# TIDA-00643_C2000.net
KiCad netlist of a schematic drawn in Altium Designer
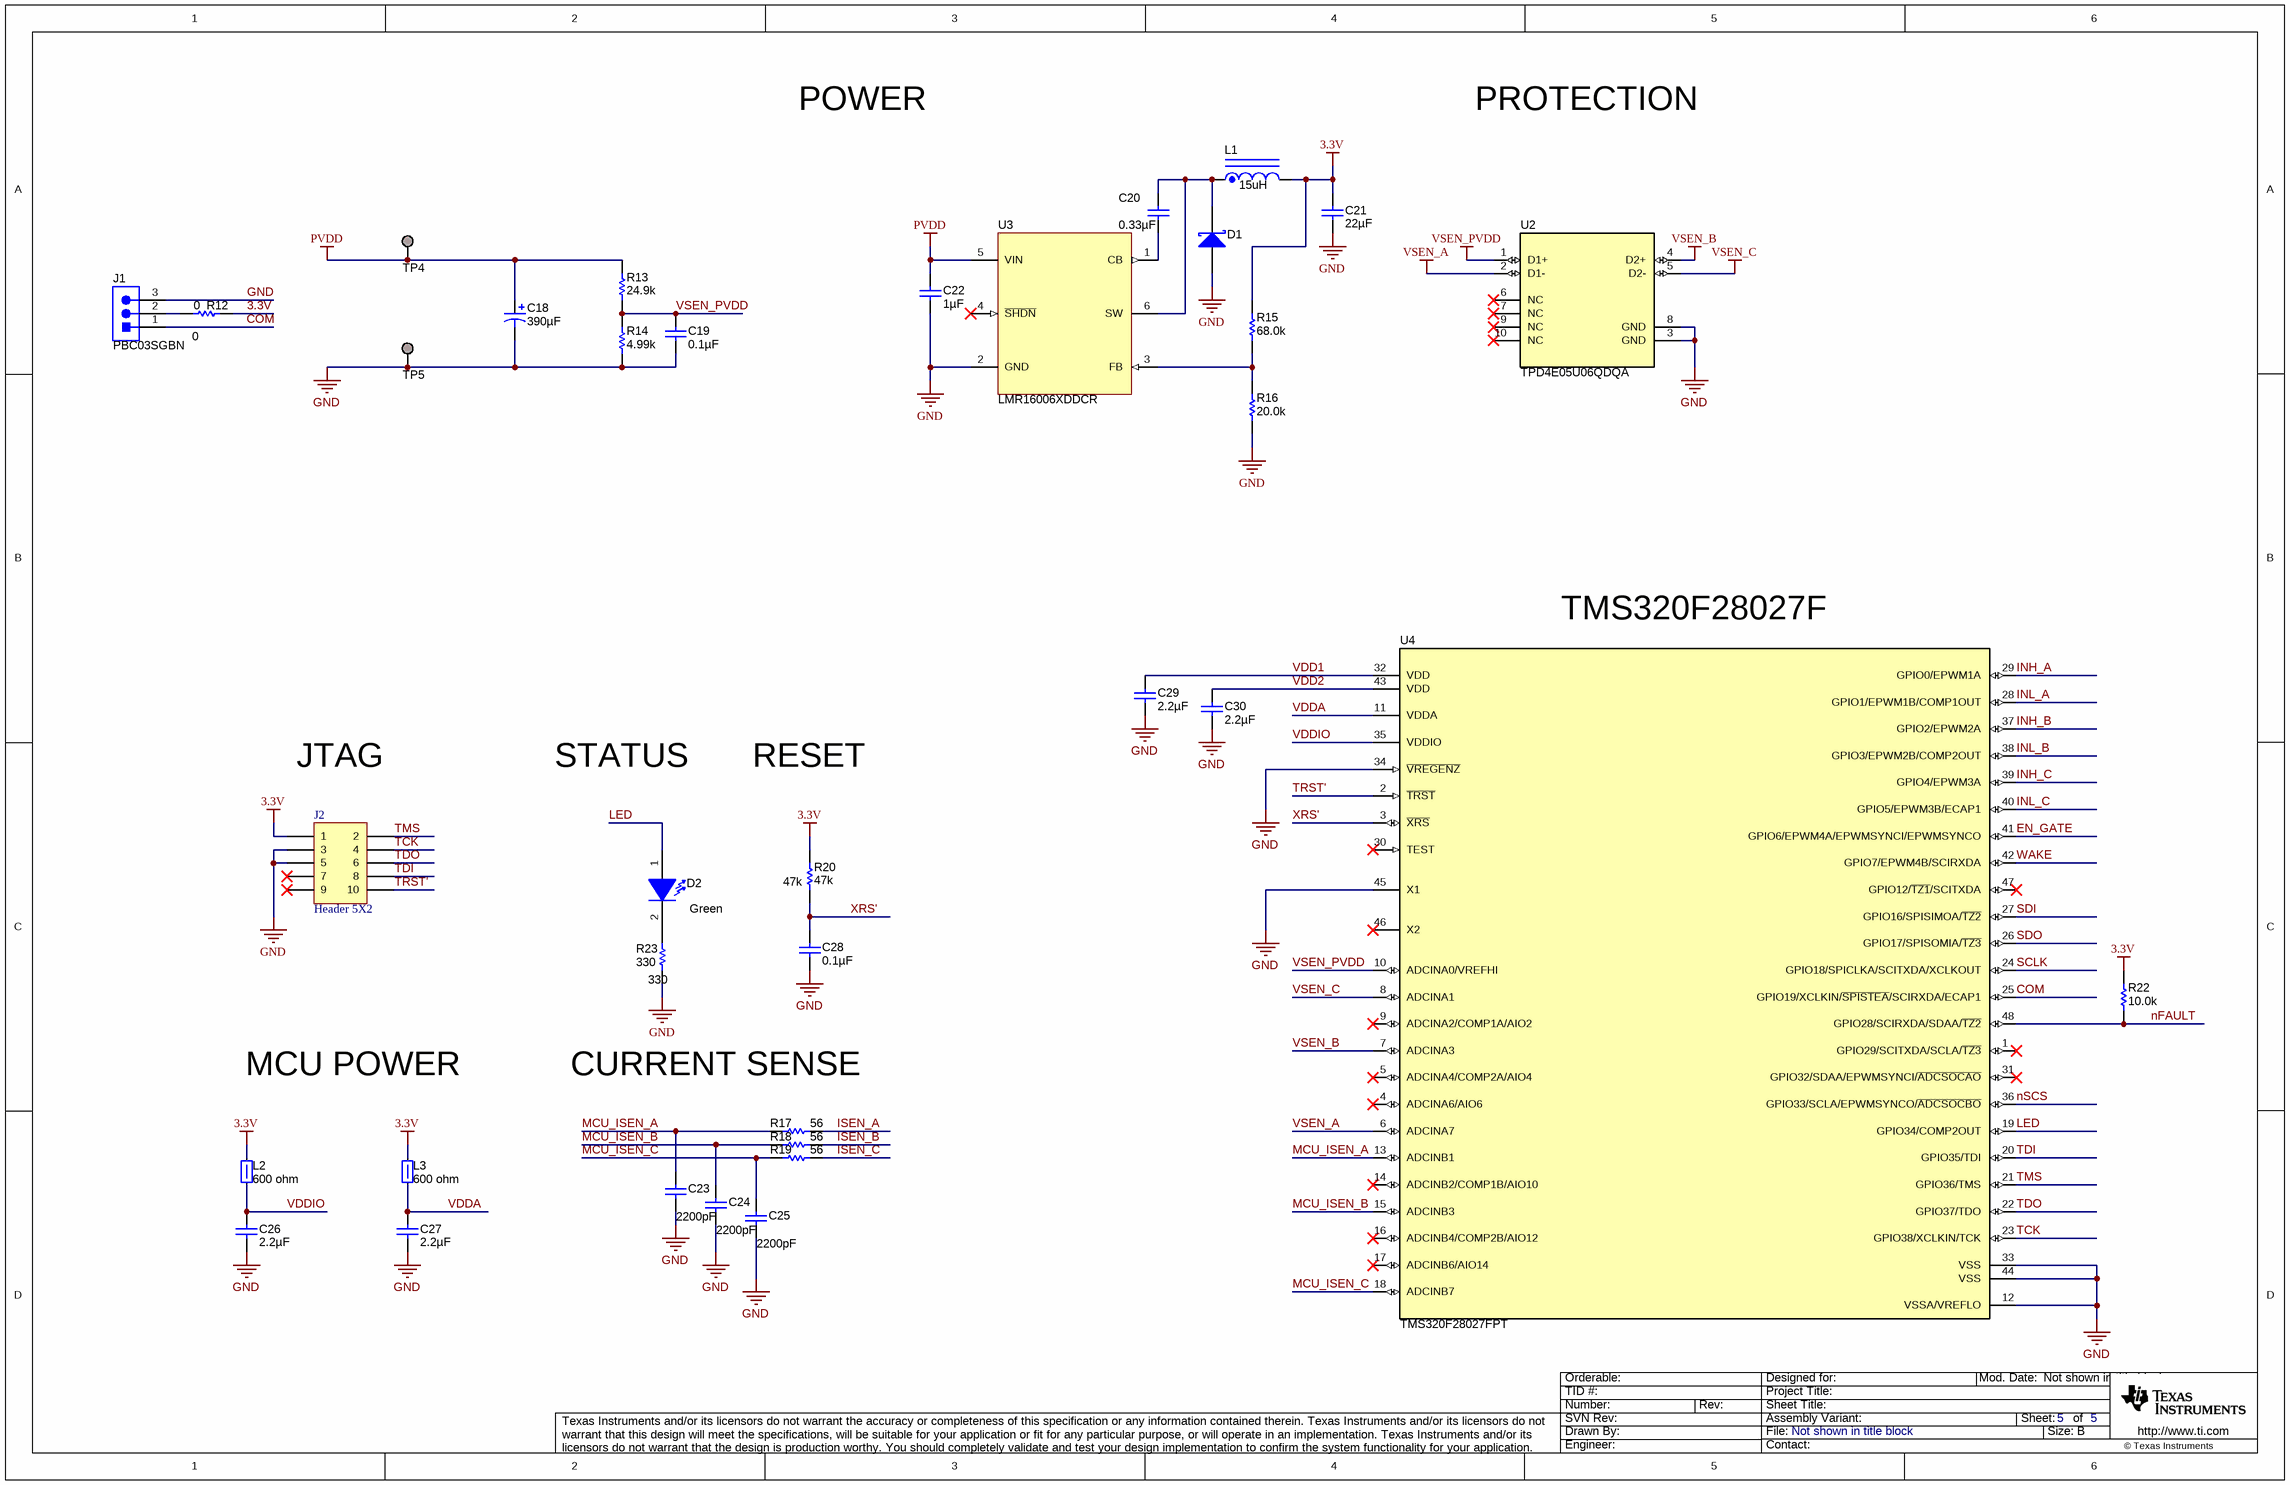
[diagram p0: TIDA-00643_C2000.SchDoc]

(export (version "E")
  (design (tool "Eeschema 10.0.6"))
  (components
    (comp (ref "C18")
      (value "EEE-FPV391UAP")
      (footprint "CAPAE1030X1080")
      (description "CAP, AL, 390 µF, 35 V, +/- 20%, 0.08 ohm, SMD")
      (fields
        (field (name "VALUEDISPLAYED") "390µF")
        (field (name "MANUFACTURER") "Panasonic")
        (field (name "PUBLISHER") "Texas Instruments")
      )
      (libsource (lib "Capacitor_Aluminum") (part "EEE-FPV391UAP"))
    )
    (comp (ref "C19")
      (value "885012105016")
      (footprint "0402L")
      (description "CAP, CERM, 0.1 µF, 16 V, +/- 20%, X5R, 0402")
      (fields
        (field (name "VALUEDISPLAYED") "0.1µF")
        (field (name "MANUFACTURER") "Wurth Elektronik")
        (field (name "PUBLISHER") "Texas Instruments")
      )
      (libsource (lib "Capacitor_Ceramic") (part "885012105016"))
    )
    (comp (ref "C20")
      (value "C0603C334Z3VACTU")
      (footprint "0603L")
      (description "CAP, CERM, 0.33 µF, 25 V, +80/-20%, Y5V, 0603")
      (fields
        (field (name "VALUEDISPLAYED") "0.33µF")
        (field (name "MANUFACTURER") "Kemet")
        (field (name "PUBLISHER") "Texas Instruments")
      )
      (libsource (lib "Capacitor_Ceramic") (part "C0603C334Z3VACTU"))
    )
    (comp (ref "C21")
      (value "C2012X5R1C226K125AC")
      (footprint "0805L")
      (description "CAP, CERM, 22 µF, 16 V, +/- 10%, X5R, 0805")
      (fields
        (field (name "VALUEDISPLAYED") "22µF")
        (field (name "MANUFACTURER") "TDK")
        (field (name "PUBLISHER") "Texas Instruments")
      )
      (libsource (lib "Capacitor_Ceramic") (part "C2012X5R1C226K125AC"))
    )
    (comp (ref "C22")
      (value "GMK107BJ105KA-T")
      (footprint "0603L")
      (description "CAP, CERM, 1 µF, 35 V, +/- 10%, X5R, 0603")
      (fields
        (field (name "VALUEDISPLAYED") "1µF")
        (field (name "MANUFACTURER") "Taiyo Yuden")
        (field (name "PUBLISHER") "Texas Instruments")
      )
      (libsource (lib "Capacitor_Ceramic") (part "GMK107BJ105KA-T"))
    )
    (comp (ref "C23")
      (value "GRM155R71C222KA01D")
      (footprint "0402L")
      (description "CAP, CERM, 2200 pF, 16 V, +/- 10%, X7R, 0402")
      (fields
        (field (name "VALUEDISPLAYED") "2200pF")
        (field (name "MANUFACTURER") "MuRata")
        (field (name "PUBLISHER") "Texas Instruments")
      )
      (libsource (lib "Capacitor_Ceramic") (part "GRM155R71C222KA01D"))
    )
    (comp (ref "C24")
      (value "GRM155R71C222KA01D")
      (footprint "0402L")
      (description "CAP, CERM, 2200 pF, 16 V, +/- 10%, X7R, 0402")
      (fields
        (field (name "VALUEDISPLAYED") "2200pF")
        (field (name "MANUFACTURER") "MuRata")
        (field (name "PUBLISHER") "Texas Instruments")
      )
      (libsource (lib "Capacitor_Ceramic") (part "GRM155R71C222KA01D"))
    )
    (comp (ref "C25")
      (value "GRM155R71C222KA01D")
      (footprint "0402L")
      (description "CAP, CERM, 2200 pF, 16 V, +/- 10%, X7R, 0402")
      (fields
        (field (name "VALUEDISPLAYED") "2200pF")
        (field (name "MANUFACTURER") "MuRata")
        (field (name "PUBLISHER") "Texas Instruments")
      )
      (libsource (lib "Capacitor_Ceramic") (part "GRM155R71C222KA01D"))
    )
    (comp (ref "C26")
      (value "GRM188R61C225KE15D")
      (footprint "0603L")
      (description "CAP, CERM, 2.2 µF, 16 V, +/- 10%, X5R, 0603")
      (fields
        (field (name "VALUEDISPLAYED") "2.2µF")
        (field (name "MANUFACTURER") "MuRata")
        (field (name "PUBLISHER") "Texas Instruments")
      )
      (libsource (lib "Capacitor_Ceramic") (part "GRM188R61C225KE15D"))
    )
    (comp (ref "C27")
      (value "GRM188R61C225KE15D")
      (footprint "0603L")
      (description "CAP, CERM, 2.2 µF, 16 V, +/- 10%, X5R, 0603")
      (fields
        (field (name "VALUEDISPLAYED") "2.2µF")
        (field (name "MANUFACTURER") "MuRata")
        (field (name "PUBLISHER") "Texas Instruments")
      )
      (libsource (lib "Capacitor_Ceramic") (part "GRM188R61C225KE15D"))
    )
    (comp (ref "C28")
      (value "885012105016")
      (footprint "0402L")
      (description "CAP, CERM, 0.1 µF, 16 V, +/- 20%, X5R, 0402")
      (fields
        (field (name "VALUEDISPLAYED") "0.1µF")
        (field (name "MANUFACTURER") "Wurth Elektronik")
        (field (name "PUBLISHER") "Texas Instruments")
      )
      (libsource (lib "Capacitor_Ceramic") (part "885012105016"))
    )
    (comp (ref "C29")
      (value "GRM188R61C225KE15D")
      (footprint "0603L")
      (description "CAP, CERM, 2.2 µF, 16 V, +/- 10%, X5R, 0603")
      (fields
        (field (name "VALUEDISPLAYED") "2.2µF")
        (field (name "MANUFACTURER") "MuRata")
        (field (name "PUBLISHER") "Texas Instruments")
      )
      (libsource (lib "Capacitor_Ceramic") (part "GRM188R61C225KE15D"))
    )
    (comp (ref "C30")
      (value "GRM188R61C225KE15D")
      (footprint "0603L")
      (description "CAP, CERM, 2.2 µF, 16 V, +/- 10%, X5R, 0603")
      (fields
        (field (name "VALUEDISPLAYED") "2.2µF")
        (field (name "MANUFACTURER") "MuRata")
        (field (name "PUBLISHER") "Texas Instruments")
      )
      (libsource (lib "Capacitor_Ceramic") (part "GRM188R61C225KE15D"))
    )
    (comp (ref "D1")
      (value "MBR1H100SFT3G")
      (footprint "SOD-123FL")
      (description "Diode, Schottky, 100 V, 1 A, SOD-123FL")
      (fields (field (name "MANUFACTURER") "ON Semiconductor") (field (name "PUBLISHER") "Texas Instruments"))
      (libsource (lib "Diode") (part "MBR1H100SFT3G"))
    )
    (comp (ref "D2")
      (value "Green")
      (footprint "LED_LTST-C171")
      (description "LED, Green, SMD")
      (fields
        (field (name "MANUFACTURER") "Lite-On")
        (field (name "PARTNUMBER") "LTST-C171GKT")
        (field (name "PUBLISHER") "Texas Instruments")
      )
      (libsource (lib "LED") (part "LTST-C171GKT"))
    )
    (comp (ref "J1")
      (value "PBC03SGBN")
      (footprint "Sullins_xxC03SGBN")
      (description "Header, 2.54 mm, 3x1, Gold, R/A, TH")
      (fields
        (field (name "MANUFACTURER") "Sullins Connector Solutions")
        (field (name "SYMBOLCREATOR") "a0799628")
        (field (name "PUBLISHER") "Texas Instruments")
      )
      (libsource (lib "Connectors_Sullins") (part "PBC03SGBN"))
    )
    (comp (ref "J2")
      (value "Header 5X2")
      (footprint "IDC DC3-10P 2X5P")
      (description "Header, 5-Pin, Dual row")
      (fields (field (name "PUBLISHER") "Altium Limited"))
      (libsource (lib "Miscellaneous Connectors") (part "Header 5X2"))
    )
    (comp (ref "L1")
      (value "15uH")
      (footprint "SD53")
      (description "Inductor, Shielded Drum Core, Ferrite, 15 µH, 1.1 A, 0.122 ohm, SMD")
      (fields
        (field (name "PARTNUMBER") "SD53-150-R")
        (field (name "MANUFACTURER") "Cooper Bussman")
        (field (name "SYMBOLCREATOR") "a0412235")
        (field (name "PUBLISHER") "Texas Instruments")
      )
      (libsource (lib "Inductor_Other") (part "SD53-150-R"))
    )
    (comp (ref "L2")
      (value "600 ohm")
      (footprint "0603L")
      (description "Ferrite Bead, 600 ohm @ 100 MHz, 1.3 A, 0603")
      (fields
        (field (name "PARTNUMBER") "BLM18KG601SN1D")
        (field (name "MANUFACTURER") "MuRata")
        (field (name "PUBLISHER") "Texas Instruments")
      )
      (libsource (lib "FerriteBead") (part "BLM18KG601SN1D"))
    )
    (comp (ref "L3")
      (value "600 ohm")
      (footprint "0603L")
      (description "Ferrite Bead, 600 ohm @ 100 MHz, 1.3 A, 0603")
      (fields
        (field (name "PARTNUMBER") "BLM18KG601SN1D")
        (field (name "MANUFACTURER") "MuRata")
        (field (name "PUBLISHER") "Texas Instruments")
      )
      (libsource (lib "FerriteBead") (part "BLM18KG601SN1D"))
    )
    (comp (ref "R12")
      (value "0")
      (footprint "0603L")
      (description "RES, 0, 5%, 0.1 W, 0603")
      (fields
        (field (name "PARTNUMBER") "CRCW06030000Z0EA")
        (field (name "MANUFACTURER") "Vishay-Dale")
        (field (name "VALUEDISPLAYED") "0")
        (field (name "PUBLISHER") "Texas Instruments")
      )
      (libsource (lib "Resistor_0603") (part "CRCW06030000Z0EA"))
    )
    (comp (ref "R13")
      (value "RC0603FR-0724K9L")
      (footprint "0603L")
      (description "RES, 24.9 k, 1%, 0.1 W, 0603")
      (fields
        (field (name "VALUEDISPLAYED") "24.9k")
        (field (name "MANUFACTURER") "Yageo America")
        (field (name "PUBLISHER") "Texas Instruments")
      )
      (libsource (lib "Resistor_0603") (part "RC0603FR-0724K9L"))
    )
    (comp (ref "R14")
      (value "CRCW04024K99FKED")
      (footprint "0402L")
      (description "RES, 4.99 k, 1%, 0.063 W, 0402")
      (fields
        (field (name "VALUEDISPLAYED") "4.99k")
        (field (name "MANUFACTURER") "Vishay-Dale")
        (field (name "PUBLISHER") "Texas Instruments")
      )
      (libsource (lib "Resistor_0402") (part "CRCW04024K99FKED"))
    )
    (comp (ref "R15")
      (value "RC0603FR-0768KL")
      (footprint "0603L")
      (description "RES, 68.0 k, 1%, 0.1 W, 0603")
      (fields
        (field (name "VALUEDISPLAYED") "68.0k")
        (field (name "MANUFACTURER") "Yageo America")
        (field (name "PUBLISHER") "Texas Instruments")
      )
      (libsource (lib "Resistor_0603") (part "RC0603FR-0768KL"))
    )
    (comp (ref "R16")
      (value "CRCW060320K0FKEA")
      (footprint "0603L")
      (description "RES, 20.0 k, 1%, 0.1 W, 0603")
      (fields
        (field (name "VALUEDISPLAYED") "20.0k")
        (field (name "MANUFACTURER") "Vishay-Dale")
        (field (name "PUBLISHER") "Texas Instruments")
      )
      (libsource (lib "Resistor_0603") (part "CRCW060320K0FKEA"))
    )
    (comp (ref "R17")
      (value "CRCW040256R0JNED")
      (footprint "0402L")
      (description "RES, 56, 5%, 0.063 W, 0402")
      (fields
        (field (name "VALUEDISPLAYED") "56")
        (field (name "MANUFACTURER") "Vishay-Dale")
        (field (name "PUBLISHER") "Texas Instruments")
      )
      (libsource (lib "Resistor_0402") (part "CRCW040256R0JNED"))
    )
    (comp (ref "R18")
      (value "CRCW040256R0JNED")
      (footprint "0402L")
      (description "RES, 56, 5%, 0.063 W, 0402")
      (fields
        (field (name "VALUEDISPLAYED") "56")
        (field (name "MANUFACTURER") "Vishay-Dale")
        (field (name "PUBLISHER") "Texas Instruments")
      )
      (libsource (lib "Resistor_0402") (part "CRCW040256R0JNED"))
    )
    (comp (ref "R19")
      (value "CRCW040256R0JNED")
      (footprint "0402L")
      (description "RES, 56, 5%, 0.063 W, 0402")
      (fields
        (field (name "VALUEDISPLAYED") "56")
        (field (name "MANUFACTURER") "Vishay-Dale")
        (field (name "PUBLISHER") "Texas Instruments")
      )
      (libsource (lib "Resistor_0402") (part "CRCW040256R0JNED"))
    )
    (comp (ref "R20")
      (value "47k")
      (footprint "0603L")
      (description "RES, 47 k, 5%, 0.1 W, 0603")
      (fields
        (field (name "PARTNUMBER") "CRCW060347K0JNEA")
        (field (name "MANUFACTURER") "Vishay-Dale")
        (field (name "VALUEDISPLAYED") "47k")
        (field (name "PUBLISHER") "Texas Instruments")
      )
      (libsource (lib "Resistor_0603") (part "CRCW060347K0JNEA"))
    )
    (comp (ref "R22")
      (value "RC0603FR-0710KL")
      (footprint "0603L")
      (description "RES, 10.0 k, 1%, 0.1 W, 0603")
      (fields
        (field (name "VALUEDISPLAYED") "10.0k")
        (field (name "MANUFACTURER") "Yageo America")
        (field (name "PUBLISHER") "Texas Instruments")
      )
      (libsource (lib "Resistor_0603") (part "RC0603FR-0710KL"))
    )
    (comp (ref "R23")
      (value "330")
      (footprint "0603L")
      (description "RES, 330, 5%, 0.1 W, 0603")
      (fields
        (field (name "PARTNUMBER") "CRCW0603330RJNEA")
        (field (name "MANUFACTURER") "Vishay-Dale")
        (field (name "VALUEDISPLAYED") "330")
        (field (name "PUBLISHER") "Texas Instruments")
      )
      (libsource (lib "Resistor_0603") (part "CRCW0603330RJNEA"))
    )
    (comp (ref "TP4")
      (value "TESTPOINT")
      (footprint "TESTPOINT")
      (description "TEST POINT.  No entry in BOM.")
      (fields (field (name "PUBLISHER") "Texas Instruments"))
      (libsource (lib "MiscParts") (part "TESTPOINT"))
    )
    (comp (ref "TP5")
      (value "TESTPOINT")
      (footprint "TESTPOINT")
      (description "TEST POINT.  No entry in BOM.")
      (fields (field (name "PUBLISHER") "Texas Instruments"))
      (libsource (lib "MiscParts") (part "TESTPOINT"))
    )
    (comp (ref "U2")
      (value "TPD4E05U06QDQA")
      (footprint "DQA0010A")
      (description "4 Channel Protection Solution for Super-Speed (up to 6 GBPS) Interface, DQA0010A")
      (fields
        (field (name "MANUFACTURER") "Texas Instruments")
        (field (name "SYMBOLCREATOR") "a0411947")
        (field (name "PUBLISHER") "Texas Instruments")
      )
      (libsource (lib "TI_Pre_RTM") (part "TPD4E05U06QDQA"))
    )
    (comp (ref "U3")
      (value "LMR16006XDDCR")
      (footprint "DDC0006A_N")
      (description "Wide Input Voltage Range Buck Regulator with High Efficiency Sleep Mode, DDC0006A")
      (fields
        (field (name "ALTERNATE PARTNUMBER") "LMR16006XDDCT")
        (field (name "MANUFACTURER") "Texas Instruments")
        (field (name "SYMBOLCREATOR") "x0208326")
        (field (name "PUBLISHER") "Texas Instruments")
      )
      (libsource (lib "TI_Pre_Release") (part "LMR16006XDDCR"))
    )
    (comp (ref "U4")
      (value "TMS320F28027FPT")
      (footprint "PT0048A_L")
      (description "Piccolo Microcontroller, PT0048A")
      (fields
        (field (name "ALTERNATE PARTNUMBER") "TMS320F28027FPTT")
        (field (name "MANUFACTURER") "Texas Instruments")
        (field (name "SYMBOLCREATOR") "Altium")
        (field (name "PUBLISHER") "Texas Instruments")
      )
      (libsource (lib "TI_Pre_Release") (part "TMS320F28027FPTQ"))
    )
  )
  (nets
    (net (code "1") (name "/COM") (class "Default")
      (node (ref "J1") (pin "1") (pinfunction "1_1") (pintype "passive"))
      (node (ref "U4") (pin "25") (pinfunction "GPIO19/XCLKIN/~{SPISTEA}/SCIRXDA/ECAP1_25") (pintype "bidirectional"))
    )
    (net (code "2") (name "/EN_GATE") (class "Default")
      (node (ref "U4") (pin "41") (pinfunction "GPIO6/EPWM4A/EPWMSYNCI/EPWMSYNCO_41") (pintype "bidirectional"))
    )
    (net (code "3") (name "/INH_A") (class "Default")
      (node (ref "U4") (pin "29") (pinfunction "GPIO0/EPWM1A_29") (pintype "bidirectional"))
    )
    (net (code "4") (name "/INH_B") (class "Default")
      (node (ref "U4") (pin "37") (pinfunction "GPIO2/EPWM2A_37") (pintype "bidirectional"))
    )
    (net (code "5") (name "/INH_C") (class "Default")
      (node (ref "U4") (pin "39") (pinfunction "GPIO4/EPWM3A_39") (pintype "bidirectional"))
    )
    (net (code "6") (name "/INL_A") (class "Default")
      (node (ref "U4") (pin "28") (pinfunction "GPIO1/EPWM1B/COMP1OUT_28") (pintype "bidirectional"))
    )
    (net (code "7") (name "/INL_B") (class "Default")
      (node (ref "U4") (pin "38") (pinfunction "GPIO3/EPWM2B/COMP2OUT_38") (pintype "bidirectional"))
    )
    (net (code "8") (name "/INL_C") (class "Default")
      (node (ref "U4") (pin "40") (pinfunction "GPIO5/EPWM3B/ECAP1_40") (pintype "bidirectional"))
    )
    (net (code "9") (name "/ISEN_A") (class "Default")
      (node (ref "R17") (pin "2") (pinfunction "2_2") (pintype "passive"))
    )
    (net (code "10") (name "/ISEN_B") (class "Default")
      (node (ref "R18") (pin "2") (pinfunction "2_2") (pintype "passive"))
    )
    (net (code "11") (name "/ISEN_C") (class "Default")
      (node (ref "R19") (pin "2") (pinfunction "2_2") (pintype "passive"))
    )
    (net (code "12") (name "/LED") (class "Default")
      (node (ref "D2") (pin "1") (pinfunction "A_1") (pintype "passive"))
      (node (ref "U4") (pin "19") (pinfunction "GPIO34/COMP2OUT_19") (pintype "bidirectional"))
    )
    (net (code "13") (name "/MCU_ISEN_A") (class "Default")
      (node (ref "C23") (pin "1") (pinfunction "1_1") (pintype "passive"))
      (node (ref "R17") (pin "1") (pinfunction "1_1") (pintype "passive"))
      (node (ref "U4") (pin "13") (pinfunction "ADCINB1_13") (pintype "bidirectional"))
    )
    (net (code "14") (name "/MCU_ISEN_B") (class "Default")
      (node (ref "C24") (pin "1") (pinfunction "1_1") (pintype "passive"))
      (node (ref "R18") (pin "1") (pinfunction "1_1") (pintype "passive"))
      (node (ref "U4") (pin "15") (pinfunction "ADCINB3_15") (pintype "bidirectional"))
    )
    (net (code "15") (name "/MCU_ISEN_C") (class "Default")
      (node (ref "C25") (pin "1") (pinfunction "1_1") (pintype "passive"))
      (node (ref "R19") (pin "1") (pinfunction "1_1") (pintype "passive"))
      (node (ref "U4") (pin "18") (pinfunction "ADCINB7_18") (pintype "bidirectional"))
    )
    (net (code "16") (name "/SCLK") (class "Default")
      (node (ref "U4") (pin "24") (pinfunction "GPIO18/SPICLKA/SCITXDA/XCLKOUT_24") (pintype "bidirectional"))
    )
    (net (code "17") (name "/SDI") (class "Default")
      (node (ref "U4") (pin "27") (pinfunction "GPIO16/SPISIMOA/~{TZ2}_27") (pintype "bidirectional"))
    )
    (net (code "18") (name "/SDO") (class "Default")
      (node (ref "U4") (pin "26") (pinfunction "GPIO17/SPISOMIA/~{TZ3}_26") (pintype "bidirectional"))
    )
    (net (code "19") (name "/TCK") (class "Default")
      (node (ref "J2") (pin "4") (pinfunction "4_4") (pintype "passive"))
      (node (ref "U4") (pin "23") (pinfunction "GPIO38/XCLKIN/TCK_23") (pintype "bidirectional"))
    )
    (net (code "20") (name "/TDI") (class "Default")
      (node (ref "J2") (pin "8") (pinfunction "8_8") (pintype "passive"))
      (node (ref "U4") (pin "20") (pinfunction "GPIO35/TDI_20") (pintype "bidirectional"))
    )
    (net (code "21") (name "/TDO") (class "Default")
      (node (ref "J2") (pin "6") (pinfunction "6_6") (pintype "passive"))
      (node (ref "U4") (pin "22") (pinfunction "GPIO37/TDO_22") (pintype "bidirectional"))
    )
    (net (code "22") (name "/TMS") (class "Default")
      (node (ref "J2") (pin "2") (pinfunction "2_2") (pintype "passive"))
      (node (ref "U4") (pin "21") (pinfunction "GPIO36/TMS_21") (pintype "bidirectional"))
    )
    (net (code "23") (name "/TRST'") (class "Default")
      (node (ref "J2") (pin "10") (pinfunction "10_10") (pintype "passive"))
      (node (ref "U4") (pin "2") (pinfunction "TRST_2") (pintype "input"))
    )
    (net (code "24") (name "/VDD1") (class "Default")
      (node (ref "C29") (pin "1") (pinfunction "1_1") (pintype "passive"))
      (node (ref "U4") (pin "32") (pinfunction "VDD_32") (pintype "power_in"))
    )
    (net (code "25") (name "/VDD2") (class "Default")
      (node (ref "C30") (pin "1") (pinfunction "1_1") (pintype "passive"))
      (node (ref "U4") (pin "43") (pinfunction "VDD_43") (pintype "power_in"))
    )
    (net (code "26") (name "/VDDA") (class "Default")
      (node (ref "C27") (pin "1") (pinfunction "1_1") (pintype "passive"))
      (node (ref "L3") (pin "1") (pinfunction "1_1") (pintype "passive"))
      (node (ref "U4") (pin "11") (pinfunction "VDDA_11") (pintype "power_in"))
    )
    (net (code "27") (name "/VDDIO") (class "Default")
      (node (ref "C26") (pin "1") (pinfunction "1_1") (pintype "passive"))
      (node (ref "L2") (pin "1") (pinfunction "1_1") (pintype "passive"))
      (node (ref "U4") (pin "35") (pinfunction "VDDIO_35") (pintype "power_in"))
    )
    (net (code "28") (name "/WAKE") (class "Default")
      (node (ref "U4") (pin "42") (pinfunction "GPIO7/EPWM4B/SCIRXDA_42") (pintype "bidirectional"))
    )
    (net (code "29") (name "/XRS'") (class "Default")
      (node (ref "C28") (pin "1") (pinfunction "1_1") (pintype "passive"))
      (node (ref "R20") (pin "1") (pinfunction "1_1") (pintype "passive"))
      (node (ref "U4") (pin "3") (pinfunction "XRS_3") (pintype "bidirectional"))
    )
    (net (code "30") (name "/nFAULT") (class "Default")
      (node (ref "R22") (pin "1") (pinfunction "1_1") (pintype "passive"))
      (node (ref "U4") (pin "48") (pinfunction "GPIO28/SCIRXDA/SDAA/~{TZ2}_48") (pintype "bidirectional"))
    )
    (net (code "31") (name "/nSCS") (class "Default")
      (node (ref "U4") (pin "36") (pinfunction "GPIO33/SCLA/EPWMSYNCO/~{ADCSOCBO}_36") (pintype "bidirectional"))
    )
    (net (code "32") (name "3.3V") (class "Default")
      (node (ref "C21") (pin "1") (pinfunction "1_1") (pintype "passive"))
      (node (ref "J2") (pin "1") (pinfunction "1_1") (pintype "passive"))
      (node (ref "L1") (pin "2") (pinfunction "2_2") (pintype "passive"))
      (node (ref "L2") (pin "2") (pinfunction "2_2") (pintype "passive"))
      (node (ref "L3") (pin "2") (pinfunction "2_2") (pintype "passive"))
      (node (ref "R12") (pin "2") (pinfunction "2_2") (pintype "passive"))
      (node (ref "R15") (pin "2") (pinfunction "2_2") (pintype "passive"))
      (node (ref "R20") (pin "2") (pinfunction "2_2") (pintype "passive"))
      (node (ref "R22") (pin "2") (pinfunction "2_2") (pintype "passive"))
    )
    (net (code "33") (name "GND") (class "Default")
      (node (ref "C18") (pin "2") (pinfunction "-_2") (pintype "passive"))
      (node (ref "C19") (pin "2") (pinfunction "2_2") (pintype "passive"))
      (node (ref "C21") (pin "2") (pinfunction "2_2") (pintype "passive"))
      (node (ref "C22") (pin "2") (pinfunction "2_2") (pintype "passive"))
      (node (ref "C23") (pin "2") (pinfunction "2_2") (pintype "passive"))
      (node (ref "C24") (pin "2") (pinfunction "2_2") (pintype "passive"))
      (node (ref "C25") (pin "2") (pinfunction "2_2") (pintype "passive"))
      (node (ref "C26") (pin "2") (pinfunction "2_2") (pintype "passive"))
      (node (ref "C27") (pin "2") (pinfunction "2_2") (pintype "passive"))
      (node (ref "C28") (pin "2") (pinfunction "2_2") (pintype "passive"))
      (node (ref "C29") (pin "2") (pinfunction "2_2") (pintype "passive"))
      (node (ref "C30") (pin "2") (pinfunction "2_2") (pintype "passive"))
      (node (ref "D1") (pin "2") (pinfunction "A_2") (pintype "passive"))
      (node (ref "J1") (pin "3") (pinfunction "3_3") (pintype "passive"))
      (node (ref "J2") (pin "3") (pinfunction "3_3") (pintype "passive"))
      (node (ref "J2") (pin "5") (pinfunction "5_5") (pintype "passive"))
      (node (ref "R14") (pin "1") (pinfunction "1_1") (pintype "passive"))
      (node (ref "R16") (pin "1") (pinfunction "1_1") (pintype "passive"))
      (node (ref "R23") (pin "1") (pinfunction "1_1") (pintype "passive"))
      (node (ref "TP5") (pin "1") (pintype "passive"))
      (node (ref "U2") (pin "3") (pinfunction "GND_3") (pintype "power_in"))
      (node (ref "U2") (pin "8") (pinfunction "GND_8") (pintype "power_in"))
      (node (ref "U3") (pin "2") (pinfunction "GND_2") (pintype "power_in"))
      (node (ref "U4") (pin "12") (pinfunction "VSSA/VREFLO_12") (pintype "power_in"))
      (node (ref "U4") (pin "33") (pinfunction "VSS_33") (pintype "power_in"))
      (node (ref "U4") (pin "34") (pinfunction "~{VREGENZ}_34") (pintype "input"))
      (node (ref "U4") (pin "44") (pinfunction "VSS_44") (pintype "power_in"))
      (node (ref "U4") (pin "45") (pinfunction "X1_45") (pintype "passive"))
    )
    (net (code "34") (name "Net-(D1-K)") (class "Default")
      (node (ref "C20") (pin "1") (pinfunction "1_1") (pintype "passive"))
      (node (ref "D1") (pin "1") (pinfunction "K_1") (pintype "passive"))
      (node (ref "L1") (pin "1") (pinfunction "1_1") (pintype "passive"))
      (node (ref "U3") (pin "6") (pinfunction "SW_6") (pintype "power_in"))
    )
    (net (code "35") (name "Net-(D2-K)") (class "Default")
      (node (ref "D2") (pin "2") (pinfunction "K_2") (pintype "passive"))
      (node (ref "R23") (pin "2") (pinfunction "2_2") (pintype "passive"))
    )
    (net (code "36") (name "Net-(J1-Pad2)") (class "Default")
      (node (ref "J1") (pin "2") (pinfunction "2_2") (pintype "passive"))
      (node (ref "R12") (pin "1") (pinfunction "1_1") (pintype "passive"))
    )
    (net (code "37") (name "Net-(U3-CB)") (class "Default")
      (node (ref "C20") (pin "2") (pinfunction "2_2") (pintype "passive"))
      (node (ref "U3") (pin "1") (pinfunction "CB_1") (pintype "output"))
    )
    (net (code "38") (name "Net-(U3-FB)") (class "Default")
      (node (ref "R15") (pin "1") (pinfunction "1_1") (pintype "passive"))
      (node (ref "R16") (pin "2") (pinfunction "2_2") (pintype "passive"))
      (node (ref "U3") (pin "3") (pinfunction "FB_3") (pintype "input"))
    )
    (net (code "39") (name "PVDD") (class "Default")
      (node (ref "C18") (pin "1") (pinfunction "+_1") (pintype "passive"))
      (node (ref "C22") (pin "1") (pinfunction "1_1") (pintype "passive"))
      (node (ref "R13") (pin "2") (pinfunction "2_2") (pintype "passive"))
      (node (ref "TP4") (pin "1") (pintype "passive"))
      (node (ref "U3") (pin "5") (pinfunction "VIN_5") (pintype "power_in"))
    )
    (net (code "40") (name "VSEN_A") (class "Default")
      (node (ref "U2") (pin "2") (pinfunction "D1-_2") (pintype "bidirectional"))
      (node (ref "U4") (pin "6") (pinfunction "ADCINA7_6") (pintype "bidirectional"))
    )
    (net (code "41") (name "VSEN_B") (class "Default")
      (node (ref "U2") (pin "4") (pinfunction "D2+_4") (pintype "bidirectional"))
      (node (ref "U4") (pin "7") (pinfunction "ADCINA3_7") (pintype "bidirectional"))
    )
    (net (code "42") (name "VSEN_C") (class "Default")
      (node (ref "U2") (pin "5") (pinfunction "D2-_5") (pintype "bidirectional"))
      (node (ref "U4") (pin "8") (pinfunction "ADCINA1_8") (pintype "bidirectional"))
    )
    (net (code "43") (name "VSEN_PVDD") (class "Default")
      (node (ref "C19") (pin "1") (pinfunction "1_1") (pintype "passive"))
      (node (ref "R13") (pin "1") (pinfunction "1_1") (pintype "passive"))
      (node (ref "R14") (pin "2") (pinfunction "2_2") (pintype "passive"))
      (node (ref "U2") (pin "1") (pinfunction "D1+_1") (pintype "bidirectional"))
      (node (ref "U4") (pin "10") (pinfunction "ADCINA0/VREFHI_10") (pintype "bidirectional"))
    )
    (net (code "44") (name "unconnected-(J2-Pad7)") (class "Default")
      (node (ref "J2") (pin "7") (pinfunction "7_7") (pintype "passive+no_connect"))
    )
    (net (code "45") (name "unconnected-(J2-Pad9)") (class "Default")
      (node (ref "J2") (pin "9") (pinfunction "9_9") (pintype "passive+no_connect"))
    )
    (net (code "46") (name "unconnected-(U2-NC-Pad6)") (class "Default")
      (node (ref "U2") (pin "6") (pinfunction "NC_6") (pintype "passive+no_connect"))
    )
    (net (code "47") (name "unconnected-(U2-NC-Pad7)") (class "Default")
      (node (ref "U2") (pin "7") (pinfunction "NC_7") (pintype "passive+no_connect"))
    )
    (net (code "48") (name "unconnected-(U2-NC-Pad9)") (class "Default")
      (node (ref "U2") (pin "9") (pinfunction "NC_9") (pintype "passive+no_connect"))
    )
    (net (code "49") (name "unconnected-(U2-NC-Pad10)") (class "Default")
      (node (ref "U2") (pin "10") (pinfunction "NC_10") (pintype "passive+no_connect"))
    )
    (net (code "50") (name "unconnected-(U3-SHDN-Pad4)") (class "Default")
      (node (ref "U3") (pin "4") (pinfunction "SHDN_4") (pintype "input+no_connect"))
    )
    (net (code "51") (name "unconnected-(U4-ADCINA2{slash}COMP1A{slash}AIO2-Pad9)") (class "Default")
      (node (ref "U4") (pin "9") (pinfunction "ADCINA2/COMP1A/AIO2_9") (pintype "bidirectional+no_connect"))
    )
    (net (code "52") (name "unconnected-(U4-ADCINA4{slash}COMP2A{slash}AIO4-Pad5)") (class "Default")
      (node (ref "U4") (pin "5") (pinfunction "ADCINA4/COMP2A/AIO4_5") (pintype "bidirectional+no_connect"))
    )
    (net (code "53") (name "unconnected-(U4-ADCINA6{slash}AIO6-Pad4)") (class "Default")
      (node (ref "U4") (pin "4") (pinfunction "ADCINA6/AIO6_4") (pintype "bidirectional+no_connect"))
    )
    (net (code "54") (name "unconnected-(U4-ADCINB2{slash}COMP1B{slash}AIO10-Pad14)") (class "Default")
      (node (ref "U4") (pin "14") (pinfunction "ADCINB2/COMP1B/AIO10_14") (pintype "bidirectional+no_connect"))
    )
    (net (code "55") (name "unconnected-(U4-ADCINB4{slash}COMP2B{slash}AIO12-Pad16)") (class "Default")
      (node (ref "U4") (pin "16") (pinfunction "ADCINB4/COMP2B/AIO12_16") (pintype "bidirectional+no_connect"))
    )
    (net (code "56") (name "unconnected-(U4-ADCINB6{slash}AIO14-Pad17)") (class "Default")
      (node (ref "U4") (pin "17") (pinfunction "ADCINB6/AIO14_17") (pintype "bidirectional+no_connect"))
    )
    (net (code "57") (name "unconnected-(U4-GPIO12{slash}~{TZ1}{slash}SCITXDA-Pad47)") (class "Default")
      (node (ref "U4") (pin "47") (pinfunction "GPIO12/~{TZ1}/SCITXDA_47") (pintype "bidirectional+no_connect"))
    )
    (net (code "58") (name "unconnected-(U4-GPIO29{slash}SCITXDA{slash}SCLA{slash}~{TZ3}-Pad1)") (class "Default")
      (node (ref "U4") (pin "1") (pinfunction "GPIO29/SCITXDA/SCLA/~{TZ3}_1") (pintype "bidirectional+no_connect"))
    )
    (net (code "59") (name "unconnected-(U4-GPIO32{slash}SDAA{slash}EPWMSYNCI{slash}~{ADCSOCAO}-Pad31)") (class "Default")
      (node (ref "U4") (pin "31") (pinfunction "GPIO32/SDAA/EPWMSYNCI/~{ADCSOCAO}_31") (pintype "bidirectional+no_connect"))
    )
    (net (code "60") (name "unconnected-(U4-TEST-Pad30)") (class "Default")
      (node (ref "U4") (pin "30") (pinfunction "TEST_30") (pintype "input+no_connect"))
    )
    (net (code "61") (name "unconnected-(U4-X2-Pad46)") (class "Default")
      (node (ref "U4") (pin "46") (pinfunction "X2_46") (pintype "passive+no_connect"))
    )
  )
)
